# MPU6050.net
KiCad netlist of a schematic drawn in EAGLE
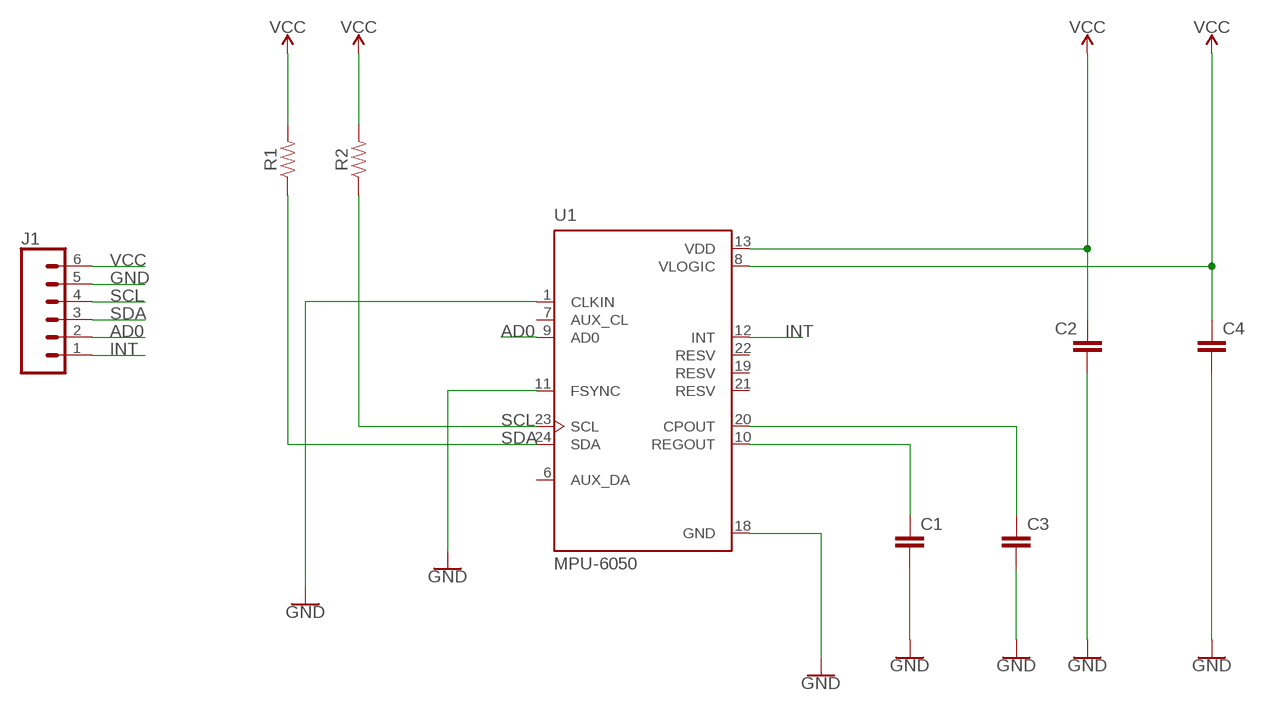
[diagram p0: schematic, sheet 1]

(export (version "E")
  (design (tool "Eeschema 10.0.6"))
  (components
    (comp (ref "C1")
      (value "C-EU050-035X075")
      (footprint "eagle-import:C050-035X075")
      (libsource (lib "eagle-import") (part "C-EU050-035X075"))
    )
    (comp (ref "C2")
      (value "C-EU050-035X075")
      (footprint "eagle-import:C050-035X075")
      (libsource (lib "eagle-import") (part "C-EU050-035X075"))
    )
    (comp (ref "C3")
      (value "C-EU050-035X075")
      (footprint "eagle-import:C050-035X075")
      (libsource (lib "eagle-import") (part "C-EU050-035X075"))
    )
    (comp (ref "C4")
      (value "C-EU050-035X075")
      (footprint "eagle-import:C050-035X075")
      (libsource (lib "eagle-import") (part "C-EU050-035X075"))
    )
    (comp (ref "J1")
      (value "CONN_06NO_SILK_FEMALE_PTH")
      (footprint "eagle-import:1X06_NO_SILK")
      (libsource (lib "eagle-import") (part "CONN_06NO_SILK_FEMALE_PTH"))
    )
    (comp (ref "R1")
      (value "RESISTORAXIAL-0.3")
      (footprint "eagle-import:AXIAL-0.3")
      (libsource (lib "eagle-import") (part "RESISTORAXIAL-0.3"))
    )
    (comp (ref "R2")
      (value "RESISTORAXIAL-0.3")
      (footprint "eagle-import:AXIAL-0.3")
      (libsource (lib "eagle-import") (part "RESISTORAXIAL-0.3"))
    )
    (comp (ref "U1")
      (value "MPU-6050")
      (footprint "eagle-import:QFN50P400X400X95-24N")
      (fields (field (name "DIGI-KEY_PART_NUMBER") "1428-1007-1-ND") (field (name "MF") "TDK InvenSense"))
      (libsource (lib "eagle-import") (part "MPU-6050"))
    )
  )
  (nets
    (net (code "1") (name "/AD0") (class "Default")
      (node (ref "J1") (pin "2") (pinfunction "2_2") (pintype "passive"))
      (node (ref "U1") (pin "9") (pinfunction "AD0_9") (pintype "input"))
    )
    (net (code "2") (name "/INT") (class "Default")
      (node (ref "J1") (pin "1") (pinfunction "1_1") (pintype "passive"))
      (node (ref "U1") (pin "12") (pinfunction "INT_12") (pintype "output"))
    )
    (net (code "3") (name "/SCL") (class "Default")
      (node (ref "J1") (pin "4") (pinfunction "4_4") (pintype "passive"))
      (node (ref "R2") (pin "P$1") (pinfunction "1_P$1") (pintype "passive"))
      (node (ref "U1") (pin "23") (pinfunction "SCL_23") (pintype "input"))
    )
    (net (code "4") (name "/SDA") (class "Default")
      (node (ref "J1") (pin "3") (pinfunction "3_3") (pintype "passive"))
      (node (ref "R1") (pin "P$1") (pinfunction "1_P$1") (pintype "passive"))
      (node (ref "U1") (pin "24") (pinfunction "SDA_24") (pintype "bidirectional"))
    )
    (net (code "5") (name "GND") (class "Default")
      (node (ref "C1") (pin "2") (pinfunction "2_2") (pintype "passive"))
      (node (ref "C2") (pin "2") (pinfunction "2_2") (pintype "passive"))
      (node (ref "C3") (pin "2") (pinfunction "2_2") (pintype "passive"))
      (node (ref "C4") (pin "2") (pinfunction "2_2") (pintype "passive"))
      (node (ref "J1") (pin "5") (pinfunction "5_5") (pintype "passive"))
      (node (ref "U1") (pin "1") (pinfunction "CLKIN_1") (pintype "input"))
      (node (ref "U1") (pin "11") (pinfunction "FSYNC_11") (pintype "input"))
      (node (ref "U1") (pin "18") (pinfunction "GND_18") (pintype "power_in"))
    )
    (net (code "6") (name "Net-(U1-CPOUT)") (class "Default")
      (node (ref "C3") (pin "1") (pinfunction "1_1") (pintype "passive"))
      (node (ref "U1") (pin "20") (pinfunction "CPOUT_20") (pintype "passive"))
    )
    (net (code "7") (name "Net-(U1-REGOUT)") (class "Default")
      (node (ref "C1") (pin "1") (pinfunction "1_1") (pintype "passive"))
      (node (ref "U1") (pin "10") (pinfunction "REGOUT_10") (pintype "passive"))
    )
    (net (code "8") (name "VCC") (class "Default")
      (node (ref "C2") (pin "1") (pinfunction "1_1") (pintype "passive"))
      (node (ref "C4") (pin "1") (pinfunction "1_1") (pintype "passive"))
      (node (ref "J1") (pin "6") (pinfunction "6_6") (pintype "passive"))
      (node (ref "R1") (pin "P$2") (pinfunction "2_P$2") (pintype "passive"))
      (node (ref "R2") (pin "P$2") (pinfunction "2_P$2") (pintype "passive"))
      (node (ref "U1") (pin "13") (pinfunction "VDD_13") (pintype "power_in"))
      (node (ref "U1") (pin "8") (pinfunction "VLOGIC_8") (pintype "power_in"))
    )
    (net (code "9") (name "unconnected-(U1-AUX_CL-Pad7)") (class "Default")
      (node (ref "U1") (pin "7") (pinfunction "AUX_CL_7") (pintype "input"))
    )
    (net (code "10") (name "unconnected-(U1-AUX_DA-Pad6)") (class "Default")
      (node (ref "U1") (pin "6") (pinfunction "AUX_DA_6") (pintype "bidirectional"))
    )
    (net (code "11") (name "unconnected-(U1-RESV-Pad19)") (class "Default")
      (node (ref "U1") (pin "19") (pinfunction "RESV_19") (pintype "passive"))
    )
    (net (code "12") (name "unconnected-(U1-RESV-Pad21)") (class "Default")
      (node (ref "U1") (pin "21") (pinfunction "RESV_21") (pintype "passive"))
    )
    (net (code "13") (name "unconnected-(U1-RESV-Pad22)") (class "Default")
      (node (ref "U1") (pin "22") (pinfunction "RESV_22") (pintype "passive"))
    )
  )
)
